# ut_bbr18_mb_usb.net
KiCad netlist of a schematic drawn in Altium Designer
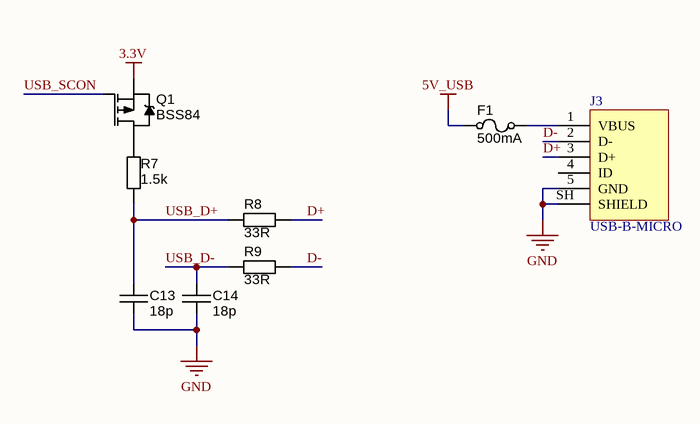
[diagram p0: ut_bbr18_mb_usb.SchDoc]

(export (version "E")
  (design (tool "Eeschema 10.0.6"))
  (components
    (comp (ref "C13")
      (value "18p")
      (footprint "CAPC1608X90N")
      (description "Capacitor SMD Cer 18pF 2% 100V NP0 0603")
      (fields (field (name "TOLERANCE") "±2%"))
      (libsource (lib "PBL - Capacitors") (part "CAPC_18p_0603_100V"))
    )
    (comp (ref "C14")
      (value "18p")
      (footprint "CAPC1608X90N")
      (description "Capacitor SMD Cer 18pF 2% 100V NP0 0603")
      (fields (field (name "TOLERANCE") "±2%"))
      (libsource (lib "PBL - Capacitors") (part "CAPC_18p_0603_100V"))
    )
    (comp (ref "F1")
      (value "500mA")
      (footprint "RESC1608X55N")
      (description "Fuse 160mA 63VDC 0603 SMD")
      (fields (field (name "Comment") "Slow-blow"))
      (libsource (lib "PBL - Fuses and Protection") (part "FUSE_160mA_0603"))
    )
    (comp (ref "J3")
      (value "USB-B-MICRO")
      (footprint "USB-B-MICRO-FCI-10104110")
      (libsource (lib "connectors") (part "USB-B-MICRO"))
    )
    (comp (ref "Q1")
      (value "BSS84")
      (footprint "SOT23-3")
      (description "MOSFET SMD P-CH 50V 130mA SOT23-3")
      (libsource (lib "PBL - Transistors") (part "MOSFET_BSS84"))
    )
    (comp (ref "R7")
      (value "1.5k")
      (footprint "RESC1608X55N")
      (description "Resistor SMD chip 10k Ohm 0.1W 5% 0603")
      (fields (field (name "TOLERANCE") "±5%"))
      (libsource (lib "") (part "RES_10K_0603_5%_1"))
    )
    (comp (ref "R8")
      (value "33R")
      (footprint "RESC1608X55N")
      (description "Resistor SMD chip 10k Ohm 0.1W 5% 0603")
      (fields (field (name "TOLERANCE") "±5%"))
      (libsource (lib "PBL - Resistors") (part "RES_10K_0603_5%"))
    )
    (comp (ref "R9")
      (value "33R")
      (footprint "RESC1608X55N")
      (description "Resistor SMD chip 10k Ohm 0.1W 5% 0603")
      (fields (field (name "TOLERANCE") "±5%"))
      (libsource (lib "PBL - Resistors") (part "RES_10K_0603_5%"))
    )
  )
  (nets
    (net (code "1") (name "/D+") (class "Default")
      (node (ref "J3") (pin "3") (pinfunction "D+_3") (pintype "passive"))
      (node (ref "R8") (pin "1") (pinfunction "1_1") (pintype "passive"))
    )
    (net (code "2") (name "/D-") (class "Default")
      (node (ref "J3") (pin "2") (pinfunction "D-_2") (pintype "passive"))
      (node (ref "R9") (pin "1") (pinfunction "1_1") (pintype "passive"))
    )
    (net (code "3") (name "/USB_D+") (class "Default")
      (node (ref "C13") (pin "2") (pintype "passive"))
      (node (ref "R7") (pin "1") (pinfunction "1_1") (pintype "passive"))
      (node (ref "R8") (pin "2") (pinfunction "2_2") (pintype "passive"))
    )
    (net (code "4") (name "/USB_D-") (class "Default")
      (node (ref "C14") (pin "1") (pintype "passive"))
      (node (ref "R9") (pin "2") (pinfunction "2_2") (pintype "passive"))
    )
    (net (code "5") (name "/USB_SCON") (class "Default")
      (node (ref "Q1") (pin "1") (pinfunction "G_1") (pintype "passive"))
    )
    (net (code "6") (name "3.3V") (class "Default")
      (node (ref "Q1") (pin "2") (pinfunction "S_2") (pintype "passive"))
    )
    (net (code "7") (name "5V_USB") (class "Default")
      (node (ref "F1") (pin "1") (pinfunction "1_1") (pintype "passive"))
    )
    (net (code "8") (name "GND") (class "Default")
      (node (ref "C13") (pin "1") (pintype "passive"))
      (node (ref "C14") (pin "2") (pintype "passive"))
      (node (ref "J3") (pin "5") (pinfunction "GND_5") (pintype "passive"))
      (node (ref "J3") (pin "SH") (pinfunction "SHIELD_SH") (pintype "passive"))
    )
    (net (code "9") (name "Net-(J3-VBUS)") (class "Default")
      (node (ref "F1") (pin "2") (pinfunction "2_2") (pintype "passive"))
      (node (ref "J3") (pin "1") (pinfunction "VBUS_1") (pintype "passive"))
    )
    (net (code "10") (name "Net-(Q1-D)") (class "Default")
      (node (ref "Q1") (pin "3") (pinfunction "D_3") (pintype "passive"))
      (node (ref "R7") (pin "2") (pinfunction "2_2") (pintype "passive"))
    )
    (net (code "11") (name "unconnected-(J3-ID-Pad4)") (class "Default")
      (node (ref "J3") (pin "4") (pinfunction "ID_4") (pintype "passive"))
    )
  )
)
